# Main_PLL.net
KiCad netlist of a schematic drawn in Altium Designer
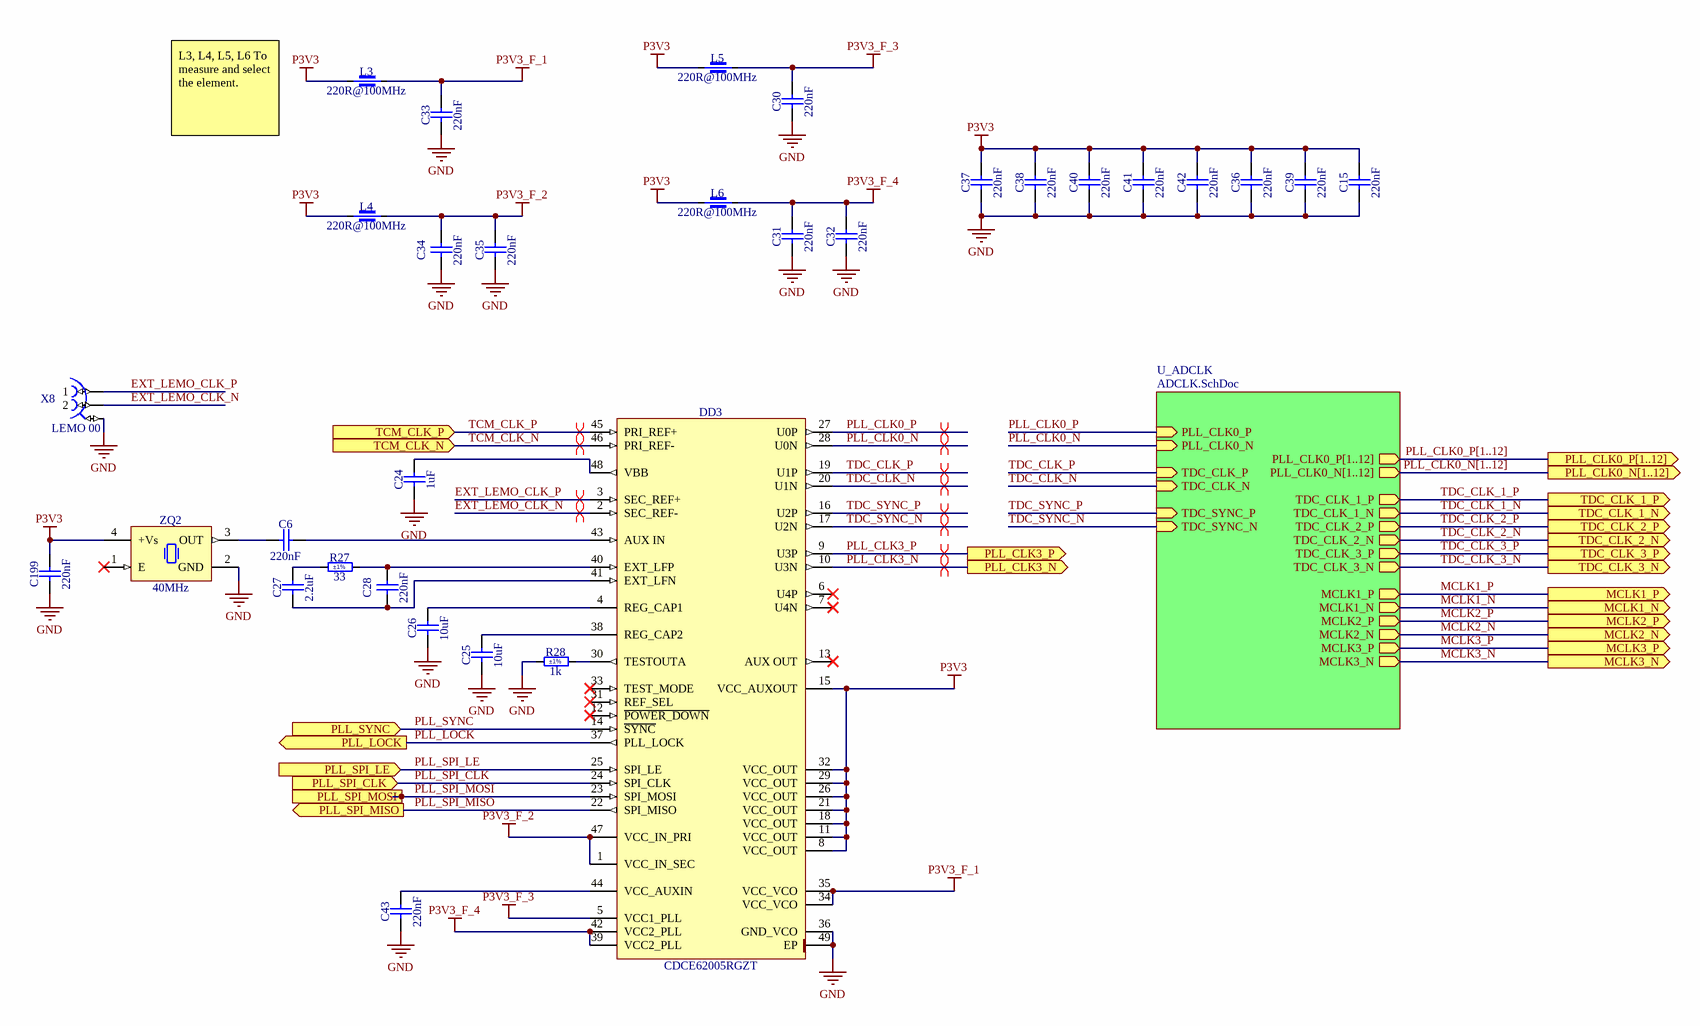
[diagram p0: Main_PLL.SchDoc]

(export (version "E")
  (design (tool "Eeschema 10.0.6"))
  (components
    (comp (ref "C6")
      (value "220nF")
      (footprint "CAPC2012X135N")
      (description "Non-polarised capacitor")
      (fields
        (field (name "PART NUMBER") "CC0805_220NF_50V_10%_X7R")
        (field (name "VOLTAGE") "50V")
        (field (name "AUTHOR") "CERN DEM JLC")
      )
      (libsource (lib "Capacitors") (part "Capacitor - non polarized"))
    )
    (comp (ref "C15")
      (value "220nF")
      (footprint "CAPC2012X135N")
      (description "Non-polarised capacitor")
      (fields
        (field (name "PART NUMBER") "CC0805_220NF_50V_10%_X7R")
        (field (name "VOLTAGE") "50V")
        (field (name "AUTHOR") "CERN DEM JLC")
      )
      (libsource (lib "Capacitors") (part "Capacitor - non polarized"))
    )
    (comp (ref "C24")
      (value "1uF")
      (footprint "CAPC2012X140N")
      (description "Non-polarised capacitor")
      (fields
        (field (name "PART NUMBER") "CC0805_1UF_25V_10%_X7R")
        (field (name "VOLTAGE") "25V")
        (field (name "AUTHOR") "CERN DEM JLC")
      )
      (libsource (lib "Capacitors") (part "Capacitor - non polarized"))
    )
    (comp (ref "C25")
      (value "10uF")
      (footprint "CAPC2012X145N")
      (description "Non-polarised capacitor")
      (fields
        (field (name "PART NUMBER") "CC0805_10UF_25V_10%_X7R")
        (field (name "VOLTAGE") "25V")
        (field (name "AUTHOR") "CERN DEM HF")
      )
      (libsource (lib "Capacitors") (part "Capacitor - non polarized"))
    )
    (comp (ref "C26")
      (value "10uF")
      (footprint "CAPC2012X145N")
      (description "Non-polarised capacitor")
      (fields
        (field (name "PART NUMBER") "CC0805_10UF_25V_10%_X7R")
        (field (name "VOLTAGE") "25V")
        (field (name "AUTHOR") "CERN DEM HF")
      )
      (libsource (lib "Capacitors") (part "Capacitor - non polarized"))
    )
    (comp (ref "C27")
      (value "2.2uF")
      (footprint "CAPC2012X140N")
      (description "Non-polarised capacitor")
      (fields
        (field (name "PART NUMBER") "CC0805_2.2UF_50V_10%_X7R")
        (field (name "VOLTAGE") "50V")
        (field (name "AUTHOR") "CERN DEM JLC")
      )
      (libsource (lib "Capacitors") (part "Capacitor - non polarized"))
    )
    (comp (ref "C28")
      (value "220nF")
      (footprint "CAPC2012X135N")
      (description "Non-polarised capacitor")
      (fields
        (field (name "PART NUMBER") "CC0805_220NF_50V_10%_X7R")
        (field (name "VOLTAGE") "50V")
        (field (name "AUTHOR") "CERN DEM JLC")
      )
      (libsource (lib "Capacitors") (part "Capacitor - non polarized"))
    )
    (comp (ref "C30")
      (value "220nF")
      (footprint "CAPC2012X135N")
      (description "Non-polarised capacitor")
      (fields
        (field (name "PART NUMBER") "CC0805_220NF_50V_10%_X7R")
        (field (name "VOLTAGE") "50V")
        (field (name "AUTHOR") "CERN DEM JLC")
      )
      (libsource (lib "Capacitors") (part "Capacitor - non polarized"))
    )
    (comp (ref "C31")
      (value "220nF")
      (footprint "CAPC2012X135N")
      (description "Non-polarised capacitor")
      (fields
        (field (name "PART NUMBER") "CC0805_220NF_50V_10%_X7R")
        (field (name "VOLTAGE") "50V")
        (field (name "AUTHOR") "CERN DEM JLC")
      )
      (libsource (lib "Capacitors") (part "Capacitor - non polarized"))
    )
    (comp (ref "C32")
      (value "220nF")
      (footprint "CAPC2012X135N")
      (description "Non-polarised capacitor")
      (fields
        (field (name "PART NUMBER") "CC0805_220NF_50V_10%_X7R")
        (field (name "VOLTAGE") "50V")
        (field (name "AUTHOR") "CERN DEM JLC")
      )
      (libsource (lib "Capacitors") (part "Capacitor - non polarized"))
    )
    (comp (ref "C33")
      (value "220nF")
      (footprint "CAPC2012X135N")
      (description "Non-polarised capacitor")
      (fields
        (field (name "PART NUMBER") "CC0805_220NF_50V_10%_X7R")
        (field (name "VOLTAGE") "50V")
        (field (name "AUTHOR") "CERN DEM JLC")
      )
      (libsource (lib "Capacitors") (part "Capacitor - non polarized"))
    )
    (comp (ref "C34")
      (value "220nF")
      (footprint "CAPC2012X135N")
      (description "Non-polarised capacitor")
      (fields
        (field (name "PART NUMBER") "CC0805_220NF_50V_10%_X7R")
        (field (name "VOLTAGE") "50V")
        (field (name "AUTHOR") "CERN DEM JLC")
      )
      (libsource (lib "Capacitors") (part "Capacitor - non polarized"))
    )
    (comp (ref "C35")
      (value "220nF")
      (footprint "CAPC2012X135N")
      (description "Non-polarised capacitor")
      (fields
        (field (name "PART NUMBER") "CC0805_220NF_50V_10%_X7R")
        (field (name "VOLTAGE") "50V")
        (field (name "AUTHOR") "CERN DEM JLC")
      )
      (libsource (lib "Capacitors") (part "Capacitor - non polarized"))
    )
    (comp (ref "C36")
      (value "220nF")
      (footprint "CAPC2012X135N")
      (description "Non-polarised capacitor")
      (fields
        (field (name "PART NUMBER") "CC0805_220NF_50V_10%_X7R")
        (field (name "VOLTAGE") "50V")
        (field (name "AUTHOR") "CERN DEM JLC")
      )
      (libsource (lib "Capacitors") (part "Capacitor - non polarized"))
    )
    (comp (ref "C37")
      (value "220nF")
      (footprint "CAPC2012X135N")
      (description "Non-polarised capacitor")
      (fields
        (field (name "PART NUMBER") "CC0805_220NF_50V_10%_X7R")
        (field (name "VOLTAGE") "50V")
        (field (name "AUTHOR") "CERN DEM JLC")
      )
      (libsource (lib "Capacitors") (part "Capacitor - non polarized"))
    )
    (comp (ref "C38")
      (value "220nF")
      (footprint "CAPC2012X135N")
      (description "Non-polarised capacitor")
      (fields
        (field (name "PART NUMBER") "CC0805_220NF_50V_10%_X7R")
        (field (name "VOLTAGE") "50V")
        (field (name "AUTHOR") "CERN DEM JLC")
      )
      (libsource (lib "Capacitors") (part "Capacitor - non polarized"))
    )
    (comp (ref "C39")
      (value "220nF")
      (footprint "CAPC2012X135N")
      (description "Non-polarised capacitor")
      (fields
        (field (name "PART NUMBER") "CC0805_220NF_50V_10%_X7R")
        (field (name "VOLTAGE") "50V")
        (field (name "AUTHOR") "CERN DEM JLC")
      )
      (libsource (lib "Capacitors") (part "Capacitor - non polarized"))
    )
    (comp (ref "C40")
      (value "220nF")
      (footprint "CAPC2012X135N")
      (description "Non-polarised capacitor")
      (fields
        (field (name "PART NUMBER") "CC0805_220NF_50V_10%_X7R")
        (field (name "VOLTAGE") "50V")
        (field (name "AUTHOR") "CERN DEM JLC")
      )
      (libsource (lib "Capacitors") (part "Capacitor - non polarized"))
    )
    (comp (ref "C41")
      (value "220nF")
      (footprint "CAPC2012X135N")
      (description "Non-polarised capacitor")
      (fields
        (field (name "PART NUMBER") "CC0805_220NF_50V_10%_X7R")
        (field (name "VOLTAGE") "50V")
        (field (name "AUTHOR") "CERN DEM JLC")
      )
      (libsource (lib "Capacitors") (part "Capacitor - non polarized"))
    )
    (comp (ref "C42")
      (value "220nF")
      (footprint "CAPC2012X135N")
      (description "Non-polarised capacitor")
      (fields
        (field (name "PART NUMBER") "CC0805_220NF_50V_10%_X7R")
        (field (name "VOLTAGE") "50V")
        (field (name "AUTHOR") "CERN DEM JLC")
      )
      (libsource (lib "Capacitors") (part "Capacitor - non polarized"))
    )
    (comp (ref "C43")
      (value "220nF")
      (footprint "CAPC2012X135N")
      (description "Non-polarised capacitor")
      (fields
        (field (name "PART NUMBER") "CC0805_220NF_50V_10%_X7R")
        (field (name "VOLTAGE") "50V")
        (field (name "AUTHOR") "CERN DEM JLC")
      )
      (libsource (lib "Capacitors") (part "Capacitor - non polarized"))
    )
    (comp (ref "C199")
      (value "220nF")
      (footprint "CAPC2012X135N")
      (description "Non-polarised capacitor")
      (fields
        (field (name "PART NUMBER") "CC0805_220NF_50V_10%_X7R")
        (field (name "VOLTAGE") "50V")
        (field (name "AUTHOR") "CERN DEM JLC")
      )
      (libsource (lib "Capacitors") (part "Capacitor - non polarized"))
    )
    (comp (ref "DD3")
      (value "CDCE62005RGZT")
      (footprint "QFN50P700X700X100-49N-S570")
      (description "5/10 Outputs Clock Generator/Jitter Cleaner with Integrated Dual VCO")
      (fields
        (field (name "MANUFACTURER") "TEXAS INSTRUMENTS")
        (field (name "MANUFACTURER PART NUMBER") "CDCE62005RGZ")
        (field (name "AUTHOR") "CERN DEM JLC")
      )
      (libsource (lib "ICs And Semiconductors") (part "CDCE62005RGZT"))
    )
    (comp (ref "L3")
      (value "220R@100MHz")
      (footprint "INDC2012X105N")
      (fields
        (field (name "PART NUMBER") "IND0805_TDK_MPZ2012S221A")
        (field (name "POWER") "3A")
        (field (name "TOLERANCE") "±25%")
        (field (name "AUTHOR") "CERN DEM HF")
      )
      (libsource (lib "Inductors & Transformers") (part "Ferrite Bead"))
    )
    (comp (ref "L4")
      (value "220R@100MHz")
      (footprint "INDC2012X105N")
      (fields
        (field (name "PART NUMBER") "IND0805_TDK_MPZ2012S221A")
        (field (name "POWER") "3A")
        (field (name "TOLERANCE") "±25%")
        (field (name "AUTHOR") "CERN DEM HF")
      )
      (libsource (lib "Inductors & Transformers") (part "Ferrite Bead"))
    )
    (comp (ref "L5")
      (value "220R@100MHz")
      (footprint "INDC2012X105N")
      (fields
        (field (name "PART NUMBER") "IND0805_TDK_MPZ2012S221A")
        (field (name "POWER") "3A")
        (field (name "TOLERANCE") "±25%")
        (field (name "AUTHOR") "CERN DEM HF")
      )
      (libsource (lib "Inductors & Transformers") (part "Ferrite Bead"))
    )
    (comp (ref "L6")
      (value "220R@100MHz")
      (footprint "INDC2012X105N")
      (fields
        (field (name "PART NUMBER") "IND0805_TDK_MPZ2012S221A")
        (field (name "POWER") "3A")
        (field (name "TOLERANCE") "±25%")
        (field (name "AUTHOR") "CERN DEM HF")
      )
      (libsource (lib "Inductors & Transformers") (part "Ferrite Bead"))
    )
    (comp (ref "R27")
      (value "33")
      (footprint "RESC2012X60N")
      (description "Resistor - 1%")
      (fields
        (field (name "TOLERANCE") "±1%")
        (field (name "PART NUMBER") "R0805_33R_1%_0.125W_100PPM")
        (field (name "POWER") "0.125W")
        (field (name "AUTHOR") "CERN DEM JLC")
      )
      (libsource (lib "Resistors") (part "Resistor - 1%"))
    )
    (comp (ref "R28")
      (value "1k")
      (footprint "RESC2012X60N")
      (description "Resistor - 1%")
      (fields
        (field (name "TOLERANCE") "±1%")
        (field (name "PART NUMBER") "R0805_1K_1%_0.125W_100PPM")
        (field (name "POWER") "0.125W")
        (field (name "AUTHOR") "CERN DEM JLC")
      )
      (libsource (lib "Resistors") (part "Resistor - 1%"))
    )
    (comp (ref "X8")
      (value "LEMO 00")
      (footprint "LEMO_EPG.00.302.NLN")
      (fields
        (field (name "PART NUMBER") "LEMO_EPG.00.302.NLN")
        (field (name "MANUFACTURER") "LEMO")
        (field (name "MANUFACTURER PART NUMBER") "EPG.00.302.NLN")
        (field (name "AUTHOR") "CERN DEM JLC")
      )
      (libsource (lib "Connectors") (part "Coax_2Female_1Shield"))
    )
    (comp (ref "ZQ2")
      (value "40MHz")
      (footprint "OSC_IQD_CFPS-73")
      (description "Oscillator 4 pins 1=E 2=GND 3=OUT 4=+Vs")
      (fields
        (field (name "PART NUMBER") "OSC_40MHZ_IQD_LFSPXO018042")
        (field (name "MANUFACTURER") "IQD FREQUENCY PRODUCTS")
        (field (name "AUTHOR") "CERN DEM JLC")
      )
      (libsource (lib "ICs And Semiconductors") (part "Oscillator 1E 2GND 3OUT 4Vs"))
    )
  )
  (nets
    (net (code "25") (name "/EXT_LEMO_CLK_N") (class "Default")
      (node (ref "DD3") (pin "2") (pinfunction "SEC_REF-_2") (pintype "input"))
      (node (ref "X8") (pin "2") (pinfunction "2_2") (pintype "bidirectional"))
    )
    (net (code "26") (name "/EXT_LEMO_CLK_P") (class "Default")
      (node (ref "DD3") (pin "3") (pinfunction "SEC_REF+_3") (pintype "input"))
      (node (ref "X8") (pin "1") (pinfunction "1_1") (pintype "bidirectional"))
    )
    (net (code "33") (name "/PLL_CLK0_N") (class "Default")
      (node (ref "DD3") (pin "28") (pinfunction "U0N_28") (pintype "output"))
    )
    (net (code "35") (name "/PLL_CLK0_P") (class "Default")
      (node (ref "DD3") (pin "27") (pinfunction "U0P_27") (pintype "output"))
    )
    (net (code "37") (name "/PLL_CLK3_N") (class "Default")
      (node (ref "DD3") (pin "10") (pinfunction "U3N_10") (pintype "output"))
    )
    (net (code "38") (name "/PLL_CLK3_P") (class "Default")
      (node (ref "DD3") (pin "9") (pinfunction "U3P_9") (pintype "output"))
    )
    (net (code "39") (name "/PLL_LOCK") (class "Default")
      (node (ref "DD3") (pin "37") (pinfunction "PLL_LOCK_37") (pintype "output"))
    )
    (net (code "40") (name "/PLL_SPI_CLK") (class "Default")
      (node (ref "DD3") (pin "24") (pinfunction "SPI_CLK_24") (pintype "input"))
    )
    (net (code "41") (name "/PLL_SPI_LE") (class "Default")
      (node (ref "DD3") (pin "25") (pinfunction "SPI_LE_25") (pintype "input"))
    )
    (net (code "42") (name "/PLL_SPI_MISO") (class "Default")
      (node (ref "DD3") (pin "22") (pinfunction "SPI_MISO_22") (pintype "output"))
    )
    (net (code "43") (name "/PLL_SPI_MOSI") (class "Default")
      (node (ref "DD3") (pin "23") (pinfunction "SPI_MOSI_23") (pintype "input"))
    )
    (net (code "44") (name "/PLL_SYNC") (class "Default")
      (node (ref "DD3") (pin "14") (pinfunction "~{SYNC}_14") (pintype "input"))
    )
    (net (code "45") (name "/TCM_CLK_N") (class "Default")
      (node (ref "DD3") (pin "46") (pinfunction "PRI_REF-_46") (pintype "input"))
    )
    (net (code "46") (name "/TCM_CLK_P") (class "Default")
      (node (ref "DD3") (pin "45") (pinfunction "PRI_REF+_45") (pintype "input"))
    )
    (net (code "53") (name "/TDC_CLK_N") (class "Default")
      (node (ref "DD3") (pin "20") (pinfunction "U1N_20") (pintype "output"))
    )
    (net (code "54") (name "/TDC_CLK_P") (class "Default")
      (node (ref "DD3") (pin "19") (pinfunction "U1P_19") (pintype "output"))
    )
    (net (code "55") (name "/TDC_SYNC_N") (class "Default")
      (node (ref "DD3") (pin "17") (pinfunction "U2N_17") (pintype "output"))
    )
    (net (code "56") (name "/TDC_SYNC_P") (class "Default")
      (node (ref "DD3") (pin "16") (pinfunction "U2P_16") (pintype "output"))
    )
    (net (code "57") (name "GND") (class "Default")
      (node (ref "C15") (pin "1") (pinfunction "1_1") (pintype "passive"))
      (node (ref "C199") (pin "1") (pinfunction "1_1") (pintype "passive"))
      (node (ref "C24") (pin "1") (pinfunction "1_1") (pintype "passive"))
      (node (ref "C25") (pin "1") (pinfunction "1_1") (pintype "passive"))
      (node (ref "C26") (pin "1") (pinfunction "1_1") (pintype "passive"))
      (node (ref "C30") (pin "1") (pinfunction "1_1") (pintype "passive"))
      (node (ref "C31") (pin "1") (pinfunction "1_1") (pintype "passive"))
      (node (ref "C32") (pin "1") (pinfunction "1_1") (pintype "passive"))
      (node (ref "C33") (pin "1") (pinfunction "1_1") (pintype "passive"))
      (node (ref "C34") (pin "1") (pinfunction "1_1") (pintype "passive"))
      (node (ref "C35") (pin "1") (pinfunction "1_1") (pintype "passive"))
      (node (ref "C36") (pin "1") (pinfunction "1_1") (pintype "passive"))
      (node (ref "C37") (pin "1") (pinfunction "1_1") (pintype "passive"))
      (node (ref "C38") (pin "1") (pinfunction "1_1") (pintype "passive"))
      (node (ref "C39") (pin "1") (pinfunction "1_1") (pintype "passive"))
      (node (ref "C40") (pin "1") (pinfunction "1_1") (pintype "passive"))
      (node (ref "C41") (pin "1") (pinfunction "1_1") (pintype "passive"))
      (node (ref "C42") (pin "1") (pinfunction "1_1") (pintype "passive"))
      (node (ref "C43") (pin "1") (pinfunction "1_1") (pintype "passive"))
      (node (ref "DD3") (pin "36") (pinfunction "GND_VCO_36") (pintype "power_in"))
      (node (ref "DD3") (pin "49") (pinfunction "EP_49") (pintype "power_in"))
      (node (ref "R28") (pin "1") (pinfunction "1_1") (pintype "passive"))
      (node (ref "X8") (pin "3") (pinfunction "3_3") (pintype "bidirectional"))
      (node (ref "ZQ2") (pin "2") (pinfunction "GND_2") (pintype "power_in"))
    )
    (net (code "58") (name "Net-(C27-Pad2)") (class "Default")
      (node (ref "C27") (pin "2") (pinfunction "2_2") (pintype "passive"))
      (node (ref "R27") (pin "1") (pinfunction "1_1") (pintype "passive"))
    )
    (net (code "59") (name "Net-(DD3-AUX_IN)") (class "Default")
      (node (ref "C6") (pin "2") (pinfunction "2_2") (pintype "passive"))
      (node (ref "DD3") (pin "43") (pinfunction "AUX_IN_43") (pintype "input"))
    )
    (net (code "60") (name "Net-(DD3-EXT_LFN)") (class "Default")
      (node (ref "C27") (pin "1") (pinfunction "1_1") (pintype "passive"))
      (node (ref "C28") (pin "1") (pinfunction "1_1") (pintype "passive"))
      (node (ref "DD3") (pin "41") (pinfunction "EXT_LFN_41") (pintype "input"))
    )
    (net (code "61") (name "Net-(DD3-EXT_LFP)") (class "Default")
      (node (ref "C28") (pin "2") (pinfunction "2_2") (pintype "passive"))
      (node (ref "DD3") (pin "40") (pinfunction "EXT_LFP_40") (pintype "input"))
      (node (ref "R27") (pin "2") (pinfunction "2_2") (pintype "passive"))
    )
    (net (code "62") (name "Net-(DD3-REG_CAP1)") (class "Default")
      (node (ref "C26") (pin "2") (pinfunction "2_2") (pintype "passive"))
      (node (ref "DD3") (pin "4") (pinfunction "REG_CAP1_4") (pintype "passive"))
    )
    (net (code "63") (name "Net-(DD3-REG_CAP2)") (class "Default")
      (node (ref "C25") (pin "2") (pinfunction "2_2") (pintype "passive"))
      (node (ref "DD3") (pin "38") (pinfunction "REG_CAP2_38") (pintype "passive"))
    )
    (net (code "64") (name "Net-(DD3-TESTOUTA)") (class "Default")
      (node (ref "DD3") (pin "30") (pinfunction "TESTOUTA_30") (pintype "output"))
      (node (ref "R28") (pin "2") (pinfunction "2_2") (pintype "passive"))
    )
    (net (code "65") (name "Net-(DD3-VBB)") (class "Default")
      (node (ref "C24") (pin "2") (pinfunction "2_2") (pintype "passive"))
      (node (ref "DD3") (pin "48") (pinfunction "VBB_48") (pintype "output"))
    )
    (net (code "66") (name "Net-(DD3-VCC_AUXIN)") (class "Default")
      (node (ref "C43") (pin "2") (pinfunction "2_2") (pintype "passive"))
      (node (ref "DD3") (pin "44") (pinfunction "VCC_AUXIN_44") (pintype "power_in"))
    )
    (net (code "67") (name "Net-(ZQ2-OUT)") (class "Default")
      (node (ref "C6") (pin "1") (pinfunction "1_1") (pintype "passive"))
      (node (ref "ZQ2") (pin "3") (pinfunction "OUT_3") (pintype "output"))
    )
    (net (code "68") (name "P3V3") (class "Default")
      (node (ref "C15") (pin "2") (pinfunction "2_2") (pintype "passive"))
      (node (ref "C199") (pin "2") (pinfunction "2_2") (pintype "passive"))
      (node (ref "C36") (pin "2") (pinfunction "2_2") (pintype "passive"))
      (node (ref "C37") (pin "2") (pinfunction "2_2") (pintype "passive"))
      (node (ref "C38") (pin "2") (pinfunction "2_2") (pintype "passive"))
      (node (ref "C39") (pin "2") (pinfunction "2_2") (pintype "passive"))
      (node (ref "C40") (pin "2") (pinfunction "2_2") (pintype "passive"))
      (node (ref "C41") (pin "2") (pinfunction "2_2") (pintype "passive"))
      (node (ref "C42") (pin "2") (pinfunction "2_2") (pintype "passive"))
      (node (ref "DD3") (pin "11") (pinfunction "VCC_OUT_11") (pintype "power_in"))
      (node (ref "DD3") (pin "15") (pinfunction "VCC_AUXOUT_15") (pintype "power_in"))
      (node (ref "DD3") (pin "18") (pinfunction "VCC_OUT_18") (pintype "power_in"))
      (node (ref "DD3") (pin "21") (pinfunction "VCC_OUT_21") (pintype "power_in"))
      (node (ref "DD3") (pin "26") (pinfunction "VCC_OUT_26") (pintype "power_in"))
      (node (ref "DD3") (pin "29") (pinfunction "VCC_OUT_29") (pintype "power_in"))
      (node (ref "DD3") (pin "32") (pinfunction "VCC_OUT_32") (pintype "power_in"))
      (node (ref "DD3") (pin "8") (pinfunction "VCC_OUT_8") (pintype "power_in"))
      (node (ref "L3") (pin "1") (pinfunction "1_1") (pintype "passive"))
      (node (ref "L4") (pin "1") (pinfunction "1_1") (pintype "passive"))
      (node (ref "L5") (pin "1") (pinfunction "1_1") (pintype "passive"))
      (node (ref "L6") (pin "1") (pinfunction "1_1") (pintype "passive"))
      (node (ref "ZQ2") (pin "4") (pinfunction "+Vs_4") (pintype "power_in"))
    )
    (net (code "69") (name "P3V3_F_1") (class "Default")
      (node (ref "C33") (pin "2") (pinfunction "2_2") (pintype "passive"))
      (node (ref "DD3") (pin "34") (pinfunction "VCC_VCO_34") (pintype "power_in"))
      (node (ref "DD3") (pin "35") (pinfunction "VCC_VCO_35") (pintype "power_in"))
      (node (ref "L3") (pin "2") (pinfunction "2_2") (pintype "passive"))
    )
    (net (code "70") (name "P3V3_F_2") (class "Default")
      (node (ref "C34") (pin "2") (pinfunction "2_2") (pintype "passive"))
      (node (ref "C35") (pin "2") (pinfunction "2_2") (pintype "passive"))
      (node (ref "DD3") (pin "1") (pinfunction "VCC_IN_SEC_1") (pintype "power_in"))
      (node (ref "DD3") (pin "47") (pinfunction "VCC_IN_PRI_47") (pintype "power_in"))
      (node (ref "L4") (pin "2") (pinfunction "2_2") (pintype "passive"))
    )
    (net (code "71") (name "P3V3_F_3") (class "Default")
      (node (ref "C30") (pin "2") (pinfunction "2_2") (pintype "passive"))
      (node (ref "DD3") (pin "5") (pinfunction "VCC1_PLL_5") (pintype "power_in"))
      (node (ref "L5") (pin "2") (pinfunction "2_2") (pintype "passive"))
    )
    (net (code "72") (name "P3V3_F_4") (class "Default")
      (node (ref "C31") (pin "2") (pinfunction "2_2") (pintype "passive"))
      (node (ref "C32") (pin "2") (pinfunction "2_2") (pintype "passive"))
      (node (ref "DD3") (pin "39") (pinfunction "VCC2_PLL_39") (pintype "power_in"))
      (node (ref "DD3") (pin "42") (pinfunction "VCC2_PLL_42") (pintype "power_in"))
      (node (ref "L6") (pin "2") (pinfunction "2_2") (pintype "passive"))
    )
    (net (code "73") (name "unconnected-(DD3-AUX_OUT-Pad13)") (class "Default")
      (node (ref "DD3") (pin "13") (pinfunction "AUX_OUT_13") (pintype "output+no_connect"))
    )
    (net (code "74") (name "unconnected-(DD3-REF_SEL-Pad31)") (class "Default")
      (node (ref "DD3") (pin "31") (pinfunction "REF_SEL_31") (pintype "input+no_connect"))
    )
    (net (code "75") (name "unconnected-(DD3-TEST_MODE-Pad33)") (class "Default")
      (node (ref "DD3") (pin "33") (pinfunction "TEST_MODE_33") (pintype "input+no_connect"))
    )
    (net (code "76") (name "unconnected-(DD3-U4N-Pad7)") (class "Default")
      (node (ref "DD3") (pin "7") (pinfunction "U4N_7") (pintype "output+no_connect"))
    )
    (net (code "77") (name "unconnected-(DD3-U4P-Pad6)") (class "Default")
      (node (ref "DD3") (pin "6") (pinfunction "U4P_6") (pintype "output+no_connect"))
    )
    (net (code "78") (name "unconnected-(DD3-~{POWER_DOWN}-Pad12)") (class "Default")
      (node (ref "DD3") (pin "12") (pinfunction "~{POWER_DOWN}_12") (pintype "input+no_connect"))
    )
    (net (code "79") (name "unconnected-(ZQ2-E-Pad1)") (class "Default")
      (node (ref "ZQ2") (pin "1") (pinfunction "E_1") (pintype "input+no_connect"))
    )
  )
)
